# Digital_IO_Protection.net
KiCad netlist of a schematic drawn in Altium Designer
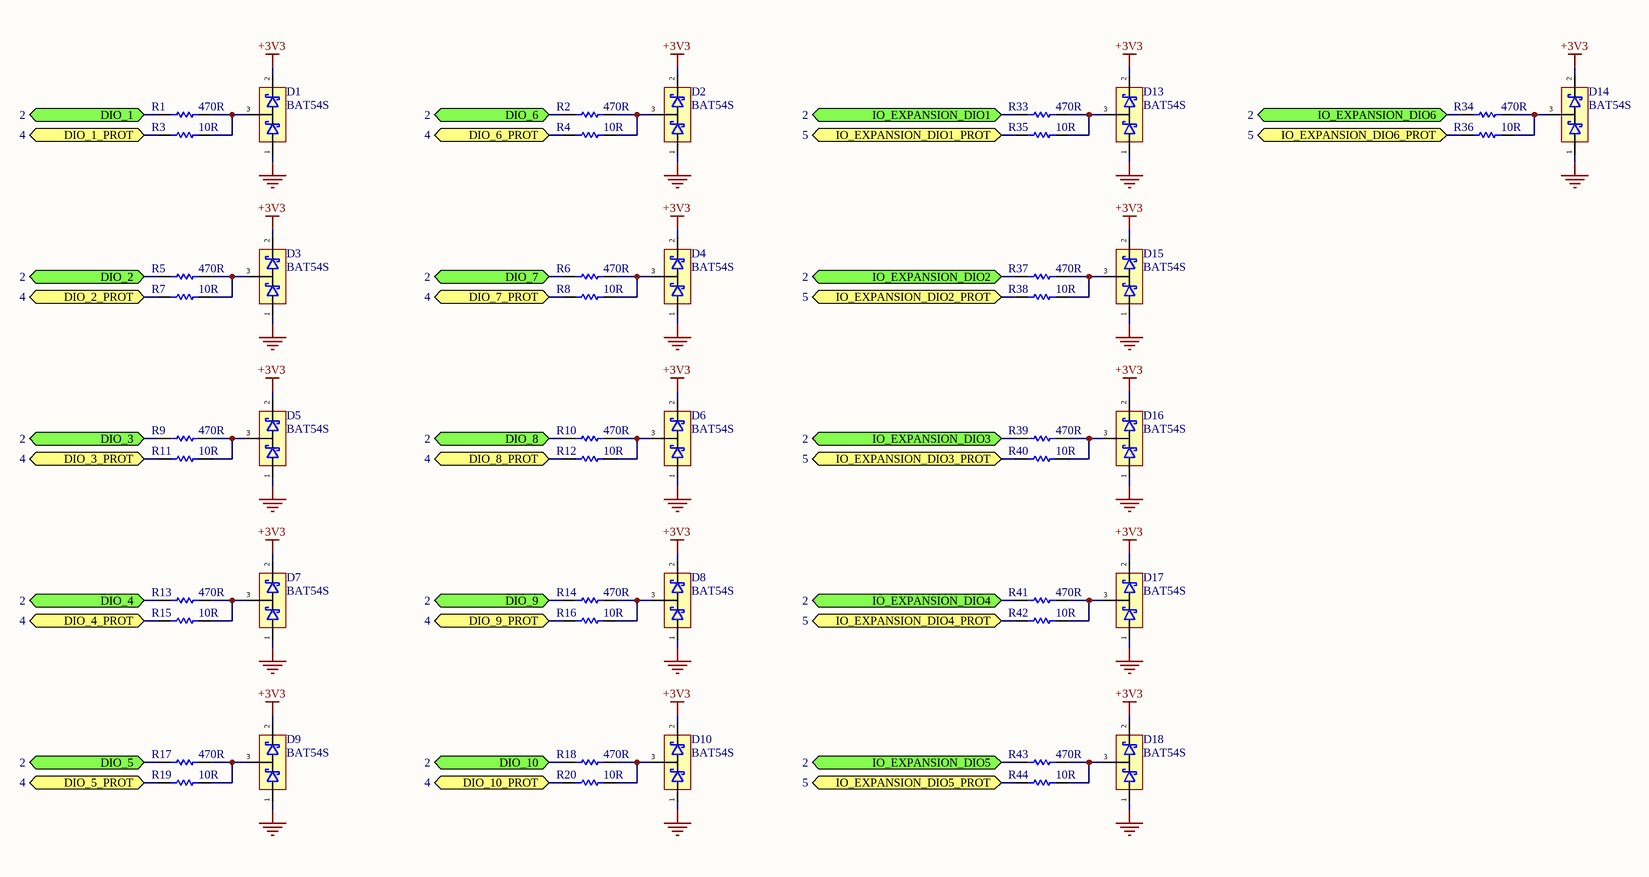
[diagram p0: Digital IO Protection.SchDoc]

(export (version "E")
  (design (tool "Eeschema 10.0.6"))
  (components
    (comp (ref "D1")
      (value "BAT54S")
      (footprint "SOT23-3")
      (description "Rectifier Diode Small Signal Schottky 40V 0.3A 5ns 3-Pin SOT-23 T/R")
      (fields
        (field (name "MANUFACTURER") "STMicroelectronics")
        (field (name "MANUFACTURER PART NUMBER") "BAT54SFILM")
      )
      (libsource (lib "MRT SCH Library") (part "Schottky Diode Array BAT54S"))
    )
    (comp (ref "D2")
      (value "BAT54S")
      (footprint "SOT23-3")
      (description "Rectifier Diode Small Signal Schottky 40V 0.3A 5ns 3-Pin SOT-23 T/R")
      (fields
        (field (name "MANUFACTURER") "STMicroelectronics")
        (field (name "MANUFACTURER PART NUMBER") "BAT54SFILM")
      )
      (libsource (lib "MRT SCH Library") (part "Schottky Diode Array BAT54S"))
    )
    (comp (ref "D3")
      (value "BAT54S")
      (footprint "SOT23-3")
      (description "Rectifier Diode Small Signal Schottky 40V 0.3A 5ns 3-Pin SOT-23 T/R")
      (fields
        (field (name "MANUFACTURER") "STMicroelectronics")
        (field (name "MANUFACTURER PART NUMBER") "BAT54SFILM")
      )
      (libsource (lib "MRT SCH Library") (part "Schottky Diode Array BAT54S"))
    )
    (comp (ref "D4")
      (value "BAT54S")
      (footprint "SOT23-3")
      (description "Rectifier Diode Small Signal Schottky 40V 0.3A 5ns 3-Pin SOT-23 T/R")
      (fields
        (field (name "MANUFACTURER") "STMicroelectronics")
        (field (name "MANUFACTURER PART NUMBER") "BAT54SFILM")
      )
      (libsource (lib "MRT SCH Library") (part "Schottky Diode Array BAT54S"))
    )
    (comp (ref "D5")
      (value "BAT54S")
      (footprint "SOT23-3")
      (description "Rectifier Diode Small Signal Schottky 40V 0.3A 5ns 3-Pin SOT-23 T/R")
      (fields
        (field (name "MANUFACTURER") "STMicroelectronics")
        (field (name "MANUFACTURER PART NUMBER") "BAT54SFILM")
      )
      (libsource (lib "MRT SCH Library") (part "Schottky Diode Array BAT54S"))
    )
    (comp (ref "D6")
      (value "BAT54S")
      (footprint "SOT23-3")
      (description "Rectifier Diode Small Signal Schottky 40V 0.3A 5ns 3-Pin SOT-23 T/R")
      (fields
        (field (name "MANUFACTURER") "STMicroelectronics")
        (field (name "MANUFACTURER PART NUMBER") "BAT54SFILM")
      )
      (libsource (lib "MRT SCH Library") (part "Schottky Diode Array BAT54S"))
    )
    (comp (ref "D7")
      (value "BAT54S")
      (footprint "SOT23-3")
      (description "Rectifier Diode Small Signal Schottky 40V 0.3A 5ns 3-Pin SOT-23 T/R")
      (fields
        (field (name "MANUFACTURER") "STMicroelectronics")
        (field (name "MANUFACTURER PART NUMBER") "BAT54SFILM")
      )
      (libsource (lib "MRT SCH Library") (part "Schottky Diode Array BAT54S"))
    )
    (comp (ref "D8")
      (value "BAT54S")
      (footprint "SOT23-3")
      (description "Rectifier Diode Small Signal Schottky 40V 0.3A 5ns 3-Pin SOT-23 T/R")
      (fields
        (field (name "MANUFACTURER") "STMicroelectronics")
        (field (name "MANUFACTURER PART NUMBER") "BAT54SFILM")
      )
      (libsource (lib "MRT SCH Library") (part "Schottky Diode Array BAT54S"))
    )
    (comp (ref "D9")
      (value "BAT54S")
      (footprint "SOT23-3")
      (description "Rectifier Diode Small Signal Schottky 40V 0.3A 5ns 3-Pin SOT-23 T/R")
      (fields
        (field (name "MANUFACTURER") "STMicroelectronics")
        (field (name "MANUFACTURER PART NUMBER") "BAT54SFILM")
      )
      (libsource (lib "MRT SCH Library") (part "Schottky Diode Array BAT54S"))
    )
    (comp (ref "D10")
      (value "BAT54S")
      (footprint "SOT23-3")
      (description "Rectifier Diode Small Signal Schottky 40V 0.3A 5ns 3-Pin SOT-23 T/R")
      (fields
        (field (name "MANUFACTURER") "STMicroelectronics")
        (field (name "MANUFACTURER PART NUMBER") "BAT54SFILM")
      )
      (libsource (lib "MRT SCH Library") (part "Schottky Diode Array BAT54S"))
    )
    (comp (ref "D13")
      (value "BAT54S")
      (footprint "SOT23-3")
      (description "Rectifier Diode Small Signal Schottky 40V 0.3A 5ns 3-Pin SOT-23 T/R")
      (fields
        (field (name "MANUFACTURER") "STMicroelectronics")
        (field (name "MANUFACTURER PART NUMBER") "BAT54SFILM")
      )
      (libsource (lib "MRT SCH Library") (part "Schottky Diode Array BAT54S"))
    )
    (comp (ref "D14")
      (value "BAT54S")
      (footprint "SOT23-3")
      (description "Rectifier Diode Small Signal Schottky 40V 0.3A 5ns 3-Pin SOT-23 T/R")
      (fields
        (field (name "MANUFACTURER") "STMicroelectronics")
        (field (name "MANUFACTURER PART NUMBER") "BAT54SFILM")
      )
      (libsource (lib "MRT SCH Library") (part "Schottky Diode Array BAT54S"))
    )
    (comp (ref "D15")
      (value "BAT54S")
      (footprint "SOT23-3")
      (description "Rectifier Diode Small Signal Schottky 40V 0.3A 5ns 3-Pin SOT-23 T/R")
      (fields
        (field (name "MANUFACTURER") "STMicroelectronics")
        (field (name "MANUFACTURER PART NUMBER") "BAT54SFILM")
      )
      (libsource (lib "MRT SCH Library") (part "Schottky Diode Array BAT54S"))
    )
    (comp (ref "D16")
      (value "BAT54S")
      (footprint "SOT23-3")
      (description "Rectifier Diode Small Signal Schottky 40V 0.3A 5ns 3-Pin SOT-23 T/R")
      (fields
        (field (name "MANUFACTURER") "STMicroelectronics")
        (field (name "MANUFACTURER PART NUMBER") "BAT54SFILM")
      )
      (libsource (lib "MRT SCH Library") (part "Schottky Diode Array BAT54S"))
    )
    (comp (ref "D17")
      (value "BAT54S")
      (footprint "SOT23-3")
      (description "Rectifier Diode Small Signal Schottky 40V 0.3A 5ns 3-Pin SOT-23 T/R")
      (fields
        (field (name "MANUFACTURER") "STMicroelectronics")
        (field (name "MANUFACTURER PART NUMBER") "BAT54SFILM")
      )
      (libsource (lib "MRT SCH Library") (part "Schottky Diode Array BAT54S"))
    )
    (comp (ref "D18")
      (value "BAT54S")
      (footprint "SOT23-3")
      (description "Rectifier Diode Small Signal Schottky 40V 0.3A 5ns 3-Pin SOT-23 T/R")
      (fields
        (field (name "MANUFACTURER") "STMicroelectronics")
        (field (name "MANUFACTURER PART NUMBER") "BAT54SFILM")
      )
      (libsource (lib "MRT SCH Library") (part "Schottky Diode Array BAT54S"))
    )
    (comp (ref "R1")
      (value "470R")
      (footprint "0805 RES")
      (fields (field (name "PUBLISHER") "Altium Limited"))
      (libsource (lib "Miscellaneous Devices") (part "Res1"))
    )
    (comp (ref "R2")
      (value "470R")
      (footprint "0805 RES")
      (fields (field (name "PUBLISHER") "Altium Limited"))
      (libsource (lib "Miscellaneous Devices") (part "Res1"))
    )
    (comp (ref "R3")
      (value "10R")
      (footprint "0603 RES")
      (fields (field (name "PUBLISHER") "Altium Limited"))
      (libsource (lib "Miscellaneous Devices") (part "Res1"))
    )
    (comp (ref "R4")
      (value "10R")
      (footprint "0603 RES")
      (fields (field (name "PUBLISHER") "Altium Limited"))
      (libsource (lib "Miscellaneous Devices") (part "Res1"))
    )
    (comp (ref "R5")
      (value "470R")
      (footprint "0805 RES")
      (fields (field (name "PUBLISHER") "Altium Limited"))
      (libsource (lib "Miscellaneous Devices") (part "Res1"))
    )
    (comp (ref "R6")
      (value "470R")
      (footprint "0805 RES")
      (fields (field (name "PUBLISHER") "Altium Limited"))
      (libsource (lib "Miscellaneous Devices") (part "Res1"))
    )
    (comp (ref "R7")
      (value "10R")
      (footprint "0603 RES")
      (fields (field (name "PUBLISHER") "Altium Limited"))
      (libsource (lib "Miscellaneous Devices") (part "Res1"))
    )
    (comp (ref "R8")
      (value "10R")
      (footprint "0603 RES")
      (fields (field (name "PUBLISHER") "Altium Limited"))
      (libsource (lib "Miscellaneous Devices") (part "Res1"))
    )
    (comp (ref "R9")
      (value "470R")
      (footprint "0805 RES")
      (fields (field (name "PUBLISHER") "Altium Limited"))
      (libsource (lib "Miscellaneous Devices") (part "Res1"))
    )
    (comp (ref "R10")
      (value "470R")
      (footprint "0805 RES")
      (fields (field (name "PUBLISHER") "Altium Limited"))
      (libsource (lib "Miscellaneous Devices") (part "Res1"))
    )
    (comp (ref "R11")
      (value "10R")
      (footprint "0603 RES")
      (fields (field (name "PUBLISHER") "Altium Limited"))
      (libsource (lib "Miscellaneous Devices") (part "Res1"))
    )
    (comp (ref "R12")
      (value "10R")
      (footprint "0603 RES")
      (fields (field (name "PUBLISHER") "Altium Limited"))
      (libsource (lib "Miscellaneous Devices") (part "Res1"))
    )
    (comp (ref "R13")
      (value "470R")
      (footprint "0805 RES")
      (fields (field (name "PUBLISHER") "Altium Limited"))
      (libsource (lib "Miscellaneous Devices") (part "Res1"))
    )
    (comp (ref "R14")
      (value "470R")
      (footprint "0805 RES")
      (fields (field (name "PUBLISHER") "Altium Limited"))
      (libsource (lib "Miscellaneous Devices") (part "Res1"))
    )
    (comp (ref "R15")
      (value "10R")
      (footprint "0603 RES")
      (fields (field (name "PUBLISHER") "Altium Limited"))
      (libsource (lib "Miscellaneous Devices") (part "Res1"))
    )
    (comp (ref "R16")
      (value "10R")
      (footprint "0603 RES")
      (fields (field (name "PUBLISHER") "Altium Limited"))
      (libsource (lib "Miscellaneous Devices") (part "Res1"))
    )
    (comp (ref "R17")
      (value "470R")
      (footprint "0805 RES")
      (fields (field (name "PUBLISHER") "Altium Limited"))
      (libsource (lib "Miscellaneous Devices") (part "Res1"))
    )
    (comp (ref "R18")
      (value "470R")
      (footprint "0805 RES")
      (fields (field (name "PUBLISHER") "Altium Limited"))
      (libsource (lib "Miscellaneous Devices") (part "Res1"))
    )
    (comp (ref "R19")
      (value "10R")
      (footprint "0603 RES")
      (fields (field (name "PUBLISHER") "Altium Limited"))
      (libsource (lib "Miscellaneous Devices") (part "Res1"))
    )
    (comp (ref "R20")
      (value "10R")
      (footprint "0603 RES")
      (fields (field (name "PUBLISHER") "Altium Limited"))
      (libsource (lib "Miscellaneous Devices") (part "Res1"))
    )
    (comp (ref "R33")
      (value "470R")
      (footprint "0805 RES")
      (fields (field (name "PUBLISHER") "Altium Limited"))
      (libsource (lib "Miscellaneous Devices") (part "Res1"))
    )
    (comp (ref "R34")
      (value "470R")
      (footprint "0805 RES")
      (fields (field (name "PUBLISHER") "Altium Limited"))
      (libsource (lib "Miscellaneous Devices") (part "Res1"))
    )
    (comp (ref "R35")
      (value "10R")
      (footprint "0603 RES")
      (fields (field (name "PUBLISHER") "Altium Limited"))
      (libsource (lib "Miscellaneous Devices") (part "Res1"))
    )
    (comp (ref "R36")
      (value "10R")
      (footprint "0603 RES")
      (fields (field (name "PUBLISHER") "Altium Limited"))
      (libsource (lib "Miscellaneous Devices") (part "Res1"))
    )
    (comp (ref "R37")
      (value "470R")
      (footprint "0805 RES")
      (fields (field (name "PUBLISHER") "Altium Limited"))
      (libsource (lib "Miscellaneous Devices") (part "Res1"))
    )
    (comp (ref "R38")
      (value "10R")
      (footprint "0603 RES")
      (fields (field (name "PUBLISHER") "Altium Limited"))
      (libsource (lib "Miscellaneous Devices") (part "Res1"))
    )
    (comp (ref "R39")
      (value "470R")
      (footprint "0805 RES")
      (fields (field (name "PUBLISHER") "Altium Limited"))
      (libsource (lib "Miscellaneous Devices") (part "Res1"))
    )
    (comp (ref "R40")
      (value "10R")
      (footprint "0603 RES")
      (fields (field (name "PUBLISHER") "Altium Limited"))
      (libsource (lib "Miscellaneous Devices") (part "Res1"))
    )
    (comp (ref "R41")
      (value "470R")
      (footprint "0805 RES")
      (fields (field (name "PUBLISHER") "Altium Limited"))
      (libsource (lib "Miscellaneous Devices") (part "Res1"))
    )
    (comp (ref "R42")
      (value "10R")
      (footprint "0603 RES")
      (fields (field (name "PUBLISHER") "Altium Limited"))
      (libsource (lib "Miscellaneous Devices") (part "Res1"))
    )
    (comp (ref "R43")
      (value "470R")
      (footprint "0805 RES")
      (fields (field (name "PUBLISHER") "Altium Limited"))
      (libsource (lib "Miscellaneous Devices") (part "Res1"))
    )
    (comp (ref "R44")
      (value "10R")
      (footprint "0603 RES")
      (fields (field (name "PUBLISHER") "Altium Limited"))
      (libsource (lib "Miscellaneous Devices") (part "Res1"))
    )
  )
  (nets
    (net (code "1") (name "+3V3") (class "Default")
      (node (ref "D1") (pin "2") (pinfunction "2_2") (pintype "passive"))
      (node (ref "D10") (pin "2") (pinfunction "2_2") (pintype "passive"))
      (node (ref "D13") (pin "2") (pinfunction "2_2") (pintype "passive"))
      (node (ref "D14") (pin "2") (pinfunction "2_2") (pintype "passive"))
      (node (ref "D15") (pin "2") (pinfunction "2_2") (pintype "passive"))
      (node (ref "D16") (pin "2") (pinfunction "2_2") (pintype "passive"))
      (node (ref "D17") (pin "2") (pinfunction "2_2") (pintype "passive"))
      (node (ref "D18") (pin "2") (pinfunction "2_2") (pintype "passive"))
      (node (ref "D2") (pin "2") (pinfunction "2_2") (pintype "passive"))
      (node (ref "D3") (pin "2") (pinfunction "2_2") (pintype "passive"))
      (node (ref "D4") (pin "2") (pinfunction "2_2") (pintype "passive"))
      (node (ref "D5") (pin "2") (pinfunction "2_2") (pintype "passive"))
      (node (ref "D6") (pin "2") (pinfunction "2_2") (pintype "passive"))
      (node (ref "D7") (pin "2") (pinfunction "2_2") (pintype "passive"))
      (node (ref "D8") (pin "2") (pinfunction "2_2") (pintype "passive"))
      (node (ref "D9") (pin "2") (pinfunction "2_2") (pintype "passive"))
    )
    (net (code "2") (name "/DIO_1") (class "Default")
      (node (ref "R1") (pin "1") (pinfunction "1_1") (pintype "passive"))
    )
    (net (code "3") (name "/DIO_1_PROT") (class "Default")
      (node (ref "R3") (pin "1") (pinfunction "1_1") (pintype "passive"))
    )
    (net (code "4") (name "/DIO_2") (class "Default")
      (node (ref "R5") (pin "1") (pinfunction "1_1") (pintype "passive"))
    )
    (net (code "5") (name "/DIO_2_PROT") (class "Default")
      (node (ref "R7") (pin "1") (pinfunction "1_1") (pintype "passive"))
    )
    (net (code "6") (name "/DIO_3") (class "Default")
      (node (ref "R9") (pin "1") (pinfunction "1_1") (pintype "passive"))
    )
    (net (code "7") (name "/DIO_3_PROT") (class "Default")
      (node (ref "R11") (pin "1") (pinfunction "1_1") (pintype "passive"))
    )
    (net (code "8") (name "/DIO_4") (class "Default")
      (node (ref "R13") (pin "1") (pinfunction "1_1") (pintype "passive"))
    )
    (net (code "9") (name "/DIO_4_PROT") (class "Default")
      (node (ref "R15") (pin "1") (pinfunction "1_1") (pintype "passive"))
    )
    (net (code "10") (name "/DIO_5") (class "Default")
      (node (ref "R17") (pin "1") (pinfunction "1_1") (pintype "passive"))
    )
    (net (code "11") (name "/DIO_5_PROT") (class "Default")
      (node (ref "R19") (pin "1") (pinfunction "1_1") (pintype "passive"))
    )
    (net (code "12") (name "/DIO_6") (class "Default")
      (node (ref "R2") (pin "1") (pinfunction "1_1") (pintype "passive"))
    )
    (net (code "13") (name "/DIO_6_PROT") (class "Default")
      (node (ref "R4") (pin "1") (pinfunction "1_1") (pintype "passive"))
    )
    (net (code "14") (name "/DIO_7") (class "Default")
      (node (ref "R6") (pin "1") (pinfunction "1_1") (pintype "passive"))
    )
    (net (code "15") (name "/DIO_7_PROT") (class "Default")
      (node (ref "R8") (pin "1") (pinfunction "1_1") (pintype "passive"))
    )
    (net (code "16") (name "/DIO_8") (class "Default")
      (node (ref "R10") (pin "1") (pinfunction "1_1") (pintype "passive"))
    )
    (net (code "17") (name "/DIO_8_PROT") (class "Default")
      (node (ref "R12") (pin "1") (pinfunction "1_1") (pintype "passive"))
    )
    (net (code "18") (name "/DIO_9") (class "Default")
      (node (ref "R14") (pin "1") (pinfunction "1_1") (pintype "passive"))
    )
    (net (code "19") (name "/DIO_9_PROT") (class "Default")
      (node (ref "R16") (pin "1") (pinfunction "1_1") (pintype "passive"))
    )
    (net (code "20") (name "/DIO_10") (class "Default")
      (node (ref "R18") (pin "1") (pinfunction "1_1") (pintype "passive"))
    )
    (net (code "21") (name "/DIO_10_PROT") (class "Default")
      (node (ref "R20") (pin "1") (pinfunction "1_1") (pintype "passive"))
    )
    (net (code "22") (name "/IO_EXPANSION_DIO1") (class "Default")
      (node (ref "R33") (pin "1") (pinfunction "1_1") (pintype "passive"))
    )
    (net (code "23") (name "/IO_EXPANSION_DIO1_PROT") (class "Default")
      (node (ref "R35") (pin "1") (pinfunction "1_1") (pintype "passive"))
    )
    (net (code "24") (name "/IO_EXPANSION_DIO2") (class "Default")
      (node (ref "R37") (pin "1") (pinfunction "1_1") (pintype "passive"))
    )
    (net (code "25") (name "/IO_EXPANSION_DIO2_PROT") (class "Default")
      (node (ref "R38") (pin "1") (pinfunction "1_1") (pintype "passive"))
    )
    (net (code "26") (name "/IO_EXPANSION_DIO3") (class "Default")
      (node (ref "R39") (pin "1") (pinfunction "1_1") (pintype "passive"))
    )
    (net (code "27") (name "/IO_EXPANSION_DIO3_PROT") (class "Default")
      (node (ref "R40") (pin "1") (pinfunction "1_1") (pintype "passive"))
    )
    (net (code "28") (name "/IO_EXPANSION_DIO4") (class "Default")
      (node (ref "R41") (pin "1") (pinfunction "1_1") (pintype "passive"))
    )
    (net (code "29") (name "/IO_EXPANSION_DIO4_PROT") (class "Default")
      (node (ref "R42") (pin "1") (pinfunction "1_1") (pintype "passive"))
    )
    (net (code "30") (name "/IO_EXPANSION_DIO5") (class "Default")
      (node (ref "R43") (pin "1") (pinfunction "1_1") (pintype "passive"))
    )
    (net (code "31") (name "/IO_EXPANSION_DIO5_PROT") (class "Default")
      (node (ref "R44") (pin "1") (pinfunction "1_1") (pintype "passive"))
    )
    (net (code "32") (name "/IO_EXPANSION_DIO6") (class "Default")
      (node (ref "R34") (pin "1") (pinfunction "1_1") (pintype "passive"))
    )
    (net (code "33") (name "/IO_EXPANSION_DIO6_PROT") (class "Default")
      (node (ref "R36") (pin "1") (pinfunction "1_1") (pintype "passive"))
    )
    (net (code "34") (name "GND") (class "Default")
      (node (ref "D1") (pin "1") (pinfunction "1_1") (pintype "passive"))
      (node (ref "D10") (pin "1") (pinfunction "1_1") (pintype "passive"))
      (node (ref "D13") (pin "1") (pinfunction "1_1") (pintype "passive"))
      (node (ref "D14") (pin "1") (pinfunction "1_1") (pintype "passive"))
      (node (ref "D15") (pin "1") (pinfunction "1_1") (pintype "passive"))
      (node (ref "D16") (pin "1") (pinfunction "1_1") (pintype "passive"))
      (node (ref "D17") (pin "1") (pinfunction "1_1") (pintype "passive"))
      (node (ref "D18") (pin "1") (pinfunction "1_1") (pintype "passive"))
      (node (ref "D2") (pin "1") (pinfunction "1_1") (pintype "passive"))
      (node (ref "D3") (pin "1") (pinfunction "1_1") (pintype "passive"))
      (node (ref "D4") (pin "1") (pinfunction "1_1") (pintype "passive"))
      (node (ref "D5") (pin "1") (pinfunction "1_1") (pintype "passive"))
      (node (ref "D6") (pin "1") (pinfunction "1_1") (pintype "passive"))
      (node (ref "D7") (pin "1") (pinfunction "1_1") (pintype "passive"))
      (node (ref "D8") (pin "1") (pinfunction "1_1") (pintype "passive"))
      (node (ref "D9") (pin "1") (pinfunction "1_1") (pintype "passive"))
    )
    (net (code "35") (name "Net-(D1-Pad3)") (class "Default")
      (node (ref "D1") (pin "3") (pinfunction "3_3") (pintype "passive"))
      (node (ref "R1") (pin "2") (pinfunction "2_2") (pintype "passive"))
      (node (ref "R3") (pin "2") (pinfunction "2_2") (pintype "passive"))
    )
    (net (code "36") (name "Net-(D2-Pad3)") (class "Default")
      (node (ref "D2") (pin "3") (pinfunction "3_3") (pintype "passive"))
      (node (ref "R2") (pin "2") (pinfunction "2_2") (pintype "passive"))
      (node (ref "R4") (pin "2") (pinfunction "2_2") (pintype "passive"))
    )
    (net (code "37") (name "Net-(D3-Pad3)") (class "Default")
      (node (ref "D3") (pin "3") (pinfunction "3_3") (pintype "passive"))
      (node (ref "R5") (pin "2") (pinfunction "2_2") (pintype "passive"))
      (node (ref "R7") (pin "2") (pinfunction "2_2") (pintype "passive"))
    )
    (net (code "38") (name "Net-(D4-Pad3)") (class "Default")
      (node (ref "D4") (pin "3") (pinfunction "3_3") (pintype "passive"))
      (node (ref "R6") (pin "2") (pinfunction "2_2") (pintype "passive"))
      (node (ref "R8") (pin "2") (pinfunction "2_2") (pintype "passive"))
    )
    (net (code "39") (name "Net-(D5-Pad3)") (class "Default")
      (node (ref "D5") (pin "3") (pinfunction "3_3") (pintype "passive"))
      (node (ref "R11") (pin "2") (pinfunction "2_2") (pintype "passive"))
      (node (ref "R9") (pin "2") (pinfunction "2_2") (pintype "passive"))
    )
    (net (code "40") (name "Net-(D6-Pad3)") (class "Default")
      (node (ref "D6") (pin "3") (pinfunction "3_3") (pintype "passive"))
      (node (ref "R10") (pin "2") (pinfunction "2_2") (pintype "passive"))
      (node (ref "R12") (pin "2") (pinfunction "2_2") (pintype "passive"))
    )
    (net (code "41") (name "Net-(D7-Pad3)") (class "Default")
      (node (ref "D7") (pin "3") (pinfunction "3_3") (pintype "passive"))
      (node (ref "R13") (pin "2") (pinfunction "2_2") (pintype "passive"))
      (node (ref "R15") (pin "2") (pinfunction "2_2") (pintype "passive"))
    )
    (net (code "42") (name "Net-(D8-Pad3)") (class "Default")
      (node (ref "D8") (pin "3") (pinfunction "3_3") (pintype "passive"))
      (node (ref "R14") (pin "2") (pinfunction "2_2") (pintype "passive"))
      (node (ref "R16") (pin "2") (pinfunction "2_2") (pintype "passive"))
    )
    (net (code "43") (name "Net-(D9-Pad3)") (class "Default")
      (node (ref "D9") (pin "3") (pinfunction "3_3") (pintype "passive"))
      (node (ref "R17") (pin "2") (pinfunction "2_2") (pintype "passive"))
      (node (ref "R19") (pin "2") (pinfunction "2_2") (pintype "passive"))
    )
    (net (code "44") (name "Net-(D10-Pad3)") (class "Default")
      (node (ref "D10") (pin "3") (pinfunction "3_3") (pintype "passive"))
      (node (ref "R18") (pin "2") (pinfunction "2_2") (pintype "passive"))
      (node (ref "R20") (pin "2") (pinfunction "2_2") (pintype "passive"))
    )
    (net (code "45") (name "Net-(D13-Pad3)") (class "Default")
      (node (ref "D13") (pin "3") (pinfunction "3_3") (pintype "passive"))
      (node (ref "R33") (pin "2") (pinfunction "2_2") (pintype "passive"))
      (node (ref "R35") (pin "2") (pinfunction "2_2") (pintype "passive"))
    )
    (net (code "46") (name "Net-(D14-Pad3)") (class "Default")
      (node (ref "D14") (pin "3") (pinfunction "3_3") (pintype "passive"))
      (node (ref "R34") (pin "2") (pinfunction "2_2") (pintype "passive"))
      (node (ref "R36") (pin "2") (pinfunction "2_2") (pintype "passive"))
    )
    (net (code "47") (name "Net-(D15-Pad3)") (class "Default")
      (node (ref "D15") (pin "3") (pinfunction "3_3") (pintype "passive"))
      (node (ref "R37") (pin "2") (pinfunction "2_2") (pintype "passive"))
      (node (ref "R38") (pin "2") (pinfunction "2_2") (pintype "passive"))
    )
    (net (code "48") (name "Net-(D16-Pad3)") (class "Default")
      (node (ref "D16") (pin "3") (pinfunction "3_3") (pintype "passive"))
      (node (ref "R39") (pin "2") (pinfunction "2_2") (pintype "passive"))
      (node (ref "R40") (pin "2") (pinfunction "2_2") (pintype "passive"))
    )
    (net (code "49") (name "Net-(D17-Pad3)") (class "Default")
      (node (ref "D17") (pin "3") (pinfunction "3_3") (pintype "passive"))
      (node (ref "R41") (pin "2") (pinfunction "2_2") (pintype "passive"))
      (node (ref "R42") (pin "2") (pinfunction "2_2") (pintype "passive"))
    )
    (net (code "50") (name "Net-(D18-Pad3)") (class "Default")
      (node (ref "D18") (pin "3") (pinfunction "3_3") (pintype "passive"))
      (node (ref "R43") (pin "2") (pinfunction "2_2") (pintype "passive"))
      (node (ref "R44") (pin "2") (pinfunction "2_2") (pintype "passive"))
    )
  )
)
